# Controll_Board_SCH.net
KiCad netlist of a schematic drawn in Altium Designer
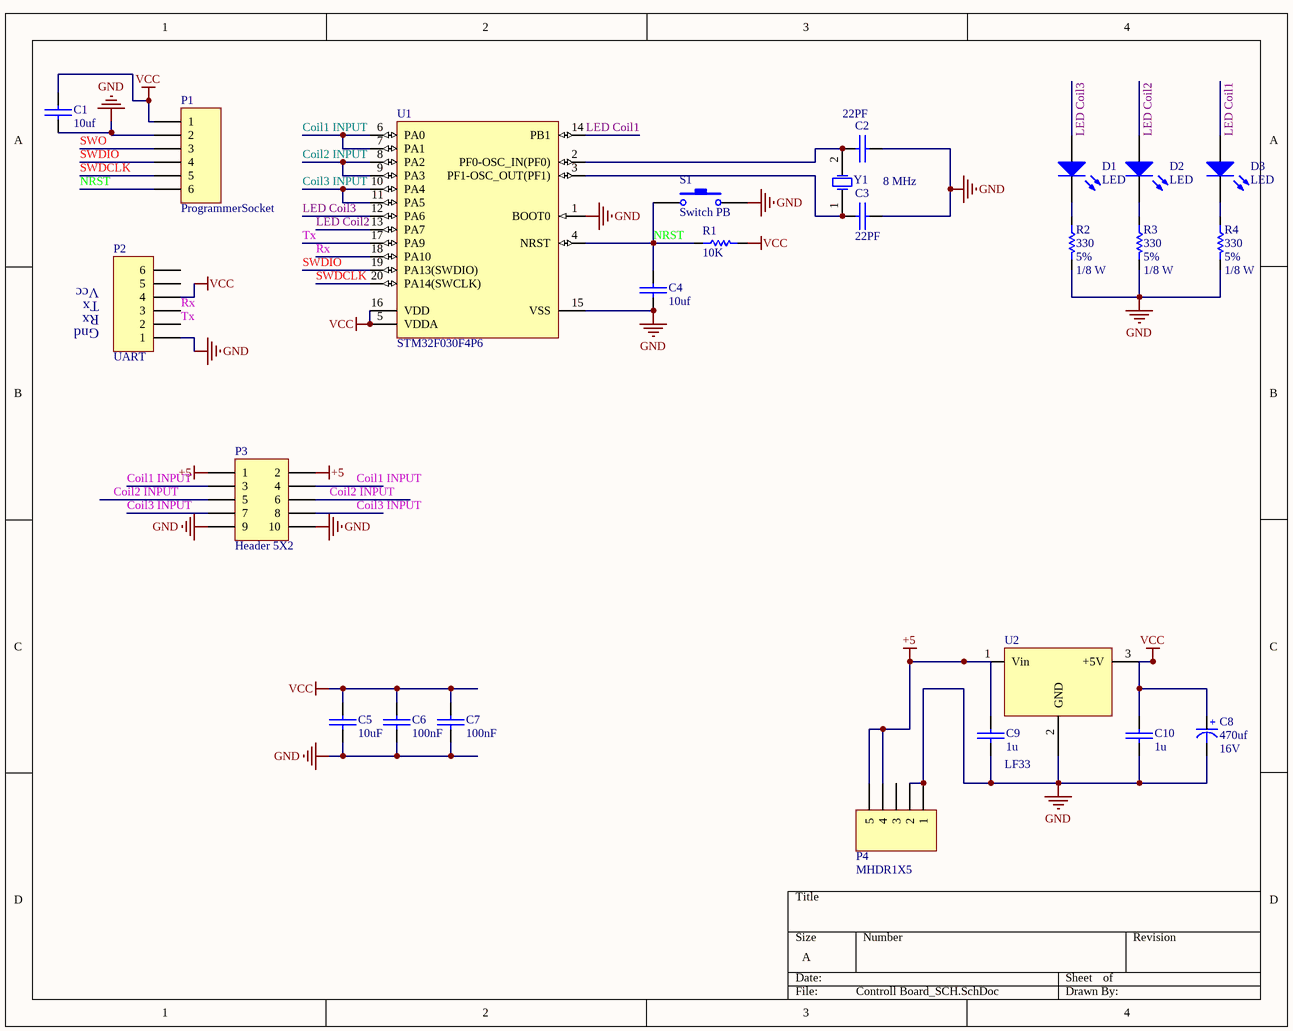
[diagram p0: Controll Board_SCH.SchDoc]

(export (version "E")
  (design (tool "Eeschema 10.0.6"))
  (components
    (comp (ref "C1")
      (value "10uf")
      (footprint "SMD_CAP_1206")
      (description "Bipolar Capacitor")
      (fields (field (name "VOLTAGE") "100V") (field (name "DESIGNER") "Saeid Jorablo"))
      (libsource (lib "My Library") (part "Cap-Bipolar"))
    )
    (comp (ref "C2")
      (value "22PF")
      (footprint "SMD_CAP_1206")
      (description "Bipolar Capacitor")
      (fields (field (name "VOLTAGE") "100V") (field (name "DESIGNER") "Saeid Jorablo"))
      (libsource (lib "My Library") (part "Cap-Bipolar"))
    )
    (comp (ref "C3")
      (value "22PF")
      (footprint "SMD_CAP_1206")
      (description "Bipolar Capacitor")
      (fields (field (name "VOLTAGE") "100V") (field (name "DESIGNER") "Saeid Jorablo"))
      (libsource (lib "My Library") (part "Cap-Bipolar"))
    )
    (comp (ref "C4")
      (value "10uf")
      (footprint "SMD_CAP_1206")
      (description "Bipolar Capacitor")
      (fields (field (name "VOLTAGE") "100V") (field (name "DESIGNER") "Saeid Jorablo"))
      (libsource (lib "My Library") (part "Cap-Bipolar"))
    )
    (comp (ref "C5")
      (value "10uF")
      (footprint "SMD_CAP_1206")
      (description "Bipolar Capacitor")
      (fields (field (name "VOLTAGE") "100V") (field (name "DESIGNER") "Saeid Jorablo"))
      (libsource (lib "My Library") (part "Cap-Bipolar"))
    )
    (comp (ref "C6")
      (value "100nF")
      (footprint "SMD_CAP_1206")
      (description "Bipolar Capacitor")
      (fields (field (name "VOLTAGE") "100V") (field (name "DESIGNER") "Saeid Jorablo"))
      (libsource (lib "My Library") (part "Cap-Bipolar"))
    )
    (comp (ref "C7")
      (value "100nF")
      (footprint "SMD_CAP_1206")
      (description "Bipolar Capacitor")
      (fields (field (name "VOLTAGE") "100V") (field (name "DESIGNER") "Saeid Jorablo"))
      (libsource (lib "My Library") (part "Cap-Bipolar"))
    )
    (comp (ref "C8")
      (value "470uf")
      (footprint "cap 01")
      (description "Polar Capacitor")
      (fields (field (name "VOLTAGE") "16V") (field (name "DESIGNER") "Saeid Jorablo"))
      (libsource (lib "My Library") (part "Cap-Polar"))
    )
    (comp (ref "C9")
      (value "1u")
      (footprint "SMD_CAP_1206")
      (description "Bipolar Capacitor")
      (fields (field (name "VOLTAGE") "100V") (field (name "DESIGNER") "Saeid Jorablo"))
      (libsource (lib "My Library") (part "Cap-Bipolar"))
    )
    (comp (ref "C10")
      (value "1u")
      (footprint "SMD_CAP_1206")
      (description "Bipolar Capacitor")
      (fields (field (name "VOLTAGE") "100V") (field (name "DESIGNER") "Saeid Jorablo"))
      (libsource (lib "My Library") (part "Cap-Bipolar"))
    )
    (comp (ref "D1")
      (value "LED")
      (footprint "My_LED3MM")
      (description "Typical INFRARED GaAs LED")
      (fields (field (name "PUBLISHER") "Altium Limited"))
      (libsource (lib "MyAltiumLib1") (part "LED"))
    )
    (comp (ref "D2")
      (value "LED")
      (footprint "My_LED3MM")
      (description "Typical INFRARED GaAs LED")
      (fields (field (name "PUBLISHER") "Altium Limited"))
      (libsource (lib "MyAltiumLib1") (part "LED"))
    )
    (comp (ref "D3")
      (value "LED")
      (footprint "My_LED3MM")
      (description "Typical INFRARED GaAs LED")
      (fields (field (name "PUBLISHER") "Altium Limited"))
      (libsource (lib "MyAltiumLib1") (part "LED"))
    )
    (comp (ref "P1")
      (value "ProgrammerSocket")
      (footprint "HDR1X6")
      (description "Header, 6-Pin")
      (fields (field (name "PUBLISHER") "Altium Limited"))
      (libsource (lib "") (part "Header 6_1"))
    )
    (comp (ref "P2")
      (value "UART")
      (footprint "HDR1X6")
      (description "Header, 6-Pin")
      (fields (field (name "PUBLISHER") "Altium Limited"))
      (libsource (lib "Miscellaneous Connectors") (part "Header 6"))
    )
    (comp (ref "P3")
      (value "Header 5X2")
      (footprint "HDR2X5")
      (description "Header, 5-Pin, Dual row")
      (fields (field (name "PUBLISHER") "Altium Limited"))
      (libsource (lib "Miscellaneous Connectors") (part "Header 5X2"))
    )
    (comp (ref "P4")
      (value "MHDR1X5")
      (footprint "MHDR1X5")
      (description "Header, 5-Pin")
      (fields (field (name "PUBLISHER") "Altium Limited"))
      (libsource (lib "Miscellaneous Connectors") (part "MHDR1X5"))
    )
    (comp (ref "R1")
      (value "10K")
      (footprint "RES 1206 (3216X08L)")
      (description "Resistor")
      (fields (field (name "TOLERANCE") "1%") (field (name "POWER") "1/8 W"))
      (libsource (lib "My Library") (part "Resistor"))
    )
    (comp (ref "R2")
      (value "330")
      (footprint "RES 1206 (3216X08L)")
      (description "Resistor")
      (fields (field (name "TOLERANCE") "5%") (field (name "POWER") "1/8 W"))
      (libsource (lib "My Library") (part "Resistor"))
    )
    (comp (ref "R3")
      (value "330")
      (footprint "RES 1206 (3216X08L)")
      (description "Resistor")
      (fields (field (name "TOLERANCE") "5%") (field (name "POWER") "1/8 W"))
      (libsource (lib "My Library") (part "Resistor"))
    )
    (comp (ref "R4")
      (value "330")
      (footprint "RES 1206 (3216X08L)")
      (description "Resistor")
      (fields (field (name "TOLERANCE") "5%") (field (name "POWER") "1/8 W"))
      (libsource (lib "My Library") (part "Resistor"))
    )
    (comp (ref "S1")
      (value "Switch PB")
      (footprint "Switch - Push to On")
      (description "Push Button Switch")
      (libsource (lib "My Library") (part "Switch PB"))
    )
    (comp (ref "U1")
      (value "STM32F030F4P6")
      (footprint "STM-TSSOP20_N")
      (libsource (lib "ST Microelectronics STM32 F0") (part "STM32F030F4P6"))
    )
    (comp (ref "U2")
      (value "LF33")
      (footprint "My_TO-220")
      (description "Regulator")
      (libsource (lib "Mylib") (part "7805"))
    )
    (comp (ref "Y1")
      (value "8 MHz")
      (footprint "XTAL Small")
      (description "XTAL Crystal")
      (libsource (lib "My Library") (part "XTAL"))
    )
  )
  (nets
    (net (code "1") (name "+5") (class "Default")
      (node (ref "C9") (pin "1") (pinfunction "+_1") (pintype "passive"))
      (node (ref "P3") (pin "1") (pinfunction "1_1") (pintype "passive"))
      (node (ref "P3") (pin "2") (pinfunction "2_2") (pintype "passive"))
      (node (ref "P4") (pin "4") (pinfunction "4_4") (pintype "passive"))
      (node (ref "P4") (pin "5") (pinfunction "5_5") (pintype "passive"))
      (node (ref "U2") (pin "1") (pinfunction "Vin_1") (pintype "power_in"))
    )
    (net (code "2") (name "/Coil1 INPUT") (class "Default")
      (node (ref "P3") (pin "3") (pinfunction "3_3") (pintype "passive"))
      (node (ref "P3") (pin "4") (pinfunction "4_4") (pintype "passive"))
      (node (ref "U1") (pin "6") (pinfunction "PA0_6") (pintype "bidirectional"))
      (node (ref "U1") (pin "7") (pinfunction "PA1_7") (pintype "bidirectional"))
    )
    (net (code "3") (name "/Coil2 INPUT") (class "Default")
      (node (ref "P3") (pin "5") (pinfunction "5_5") (pintype "passive"))
      (node (ref "P3") (pin "6") (pinfunction "6_6") (pintype "passive"))
      (node (ref "U1") (pin "8") (pinfunction "PA2_8") (pintype "bidirectional"))
      (node (ref "U1") (pin "9") (pinfunction "PA3_9") (pintype "bidirectional"))
    )
    (net (code "4") (name "/Coil3 INPUT") (class "Default")
      (node (ref "P3") (pin "7") (pinfunction "7_7") (pintype "passive"))
      (node (ref "P3") (pin "8") (pinfunction "8_8") (pintype "passive"))
      (node (ref "U1") (pin "10") (pinfunction "PA4_10") (pintype "bidirectional"))
      (node (ref "U1") (pin "11") (pinfunction "PA5_11") (pintype "bidirectional"))
    )
    (net (code "5") (name "/LED Coil1") (class "Default")
      (node (ref "D3") (pin "A") (pinfunction "A_A") (pintype "passive"))
      (node (ref "U1") (pin "14") (pinfunction "PB1_14") (pintype "bidirectional"))
    )
    (net (code "6") (name "/LED Coil2") (class "Default")
      (node (ref "D2") (pin "A") (pinfunction "A_A") (pintype "passive"))
      (node (ref "U1") (pin "13") (pinfunction "PA7_13") (pintype "bidirectional"))
    )
    (net (code "7") (name "/LED Coil3") (class "Default")
      (node (ref "D1") (pin "A") (pinfunction "A_A") (pintype "passive"))
      (node (ref "U1") (pin "12") (pinfunction "PA6_12") (pintype "bidirectional"))
    )
    (net (code "8") (name "/NRST") (class "Default")
      (node (ref "C4") (pin "2") (pinfunction "-_2") (pintype "passive"))
      (node (ref "P1") (pin "6") (pinfunction "6_6") (pintype "passive"))
      (node (ref "R1") (pin "1") (pinfunction "1_1") (pintype "passive"))
      (node (ref "S1") (pin "1") (pinfunction "1_1") (pintype "passive"))
      (node (ref "U1") (pin "4") (pinfunction "NRST_4") (pintype "bidirectional"))
    )
    (net (code "9") (name "/Rx") (class "Default")
      (node (ref "P2") (pin "3") (pinfunction "3_3") (pintype "passive"))
      (node (ref "U1") (pin "18") (pinfunction "PA10_18") (pintype "bidirectional"))
    )
    (net (code "10") (name "/SWDCLK") (class "Default")
      (node (ref "P1") (pin "5") (pinfunction "5_5") (pintype "passive"))
      (node (ref "U1") (pin "20") (pinfunction "PA14(SWCLK)_20") (pintype "bidirectional"))
    )
    (net (code "11") (name "/SWDIO") (class "Default")
      (node (ref "P1") (pin "4") (pinfunction "4_4") (pintype "passive"))
      (node (ref "U1") (pin "19") (pinfunction "PA13(SWDIO)_19") (pintype "bidirectional"))
    )
    (net (code "12") (name "/SWO") (class "Default")
      (node (ref "P1") (pin "3") (pinfunction "3_3") (pintype "passive"))
    )
    (net (code "13") (name "/Tx") (class "Default")
      (node (ref "P2") (pin "2") (pinfunction "2_2") (pintype "passive"))
      (node (ref "U1") (pin "17") (pinfunction "PA9_17") (pintype "bidirectional"))
    )
    (net (code "14") (name "GND") (class "Default")
      (node (ref "C1") (pin "1") (pinfunction "+_1") (pintype "passive"))
      (node (ref "C10") (pin "2") (pinfunction "-_2") (pintype "passive"))
      (node (ref "C2") (pin "2") (pinfunction "-_2") (pintype "passive"))
      (node (ref "C3") (pin "2") (pinfunction "-_2") (pintype "passive"))
      (node (ref "C4") (pin "1") (pinfunction "+_1") (pintype "passive"))
      (node (ref "C5") (pin "2") (pinfunction "-_2") (pintype "passive"))
      (node (ref "C6") (pin "2") (pinfunction "-_2") (pintype "passive"))
      (node (ref "C7") (pin "2") (pinfunction "-_2") (pintype "passive"))
      (node (ref "C8") (pin "2") (pinfunction "-_2") (pintype "passive"))
      (node (ref "C9") (pin "2") (pinfunction "-_2") (pintype "passive"))
      (node (ref "P1") (pin "2") (pinfunction "2_2") (pintype "passive"))
      (node (ref "P2") (pin "1") (pinfunction "1_1") (pintype "passive"))
      (node (ref "P3") (pin "10") (pinfunction "10_10") (pintype "passive"))
      (node (ref "P3") (pin "9") (pinfunction "9_9") (pintype "passive"))
      (node (ref "P4") (pin "1") (pinfunction "1_1") (pintype "passive"))
      (node (ref "P4") (pin "2") (pinfunction "2_2") (pintype "passive"))
      (node (ref "R2") (pin "2") (pinfunction "2_2") (pintype "passive"))
      (node (ref "R3") (pin "2") (pinfunction "2_2") (pintype "passive"))
      (node (ref "R4") (pin "2") (pinfunction "2_2") (pintype "passive"))
      (node (ref "S1") (pin "2") (pinfunction "2_2") (pintype "passive"))
      (node (ref "U1") (pin "1") (pinfunction "BOOT0_1") (pintype "input"))
      (node (ref "U1") (pin "15") (pinfunction "VSS_15") (pintype "power_in"))
      (node (ref "U2") (pin "2") (pinfunction "GND_2") (pintype "power_in"))
    )
    (net (code "15") (name "Net-(C2-+)") (class "Default")
      (node (ref "C2") (pin "1") (pinfunction "+_1") (pintype "passive"))
      (node (ref "U1") (pin "2") (pinfunction "PF0-OSC_IN(PF0)_2") (pintype "bidirectional"))
      (node (ref "Y1") (pin "2") (pinfunction "OSC2_2") (pintype "passive"))
    )
    (net (code "16") (name "Net-(C3-+)") (class "Default")
      (node (ref "C3") (pin "1") (pinfunction "+_1") (pintype "passive"))
      (node (ref "U1") (pin "3") (pinfunction "PF1-OSC_OUT(PF1)_3") (pintype "bidirectional"))
      (node (ref "Y1") (pin "1") (pinfunction "OSC1_1") (pintype "passive"))
    )
    (net (code "17") (name "Net-(D1-PadK)") (class "Default")
      (node (ref "D1") (pin "K") (pinfunction "K_K") (pintype "passive"))
      (node (ref "R2") (pin "1") (pinfunction "1_1") (pintype "passive"))
    )
    (net (code "18") (name "Net-(D2-PadK)") (class "Default")
      (node (ref "D2") (pin "K") (pinfunction "K_K") (pintype "passive"))
      (node (ref "R3") (pin "1") (pinfunction "1_1") (pintype "passive"))
    )
    (net (code "19") (name "Net-(D3-PadK)") (class "Default")
      (node (ref "D3") (pin "K") (pinfunction "K_K") (pintype "passive"))
      (node (ref "R4") (pin "1") (pinfunction "1_1") (pintype "passive"))
    )
    (net (code "20") (name "VCC") (class "Default")
      (node (ref "C1") (pin "2") (pinfunction "-_2") (pintype "passive"))
      (node (ref "C10") (pin "1") (pinfunction "+_1") (pintype "passive"))
      (node (ref "C5") (pin "1") (pinfunction "+_1") (pintype "passive"))
      (node (ref "C6") (pin "1") (pinfunction "+_1") (pintype "passive"))
      (node (ref "C7") (pin "1") (pinfunction "+_1") (pintype "passive"))
      (node (ref "C8") (pin "1") (pinfunction "+_1") (pintype "passive"))
      (node (ref "P1") (pin "1") (pinfunction "1_1") (pintype "passive"))
      (node (ref "P2") (pin "4") (pinfunction "4_4") (pintype "passive"))
      (node (ref "R1") (pin "2") (pinfunction "2_2") (pintype "passive"))
      (node (ref "U1") (pin "16") (pinfunction "VDD_16") (pintype "power_in"))
      (node (ref "U1") (pin "5") (pinfunction "VDDA_5") (pintype "power_in"))
      (node (ref "U2") (pin "3") (pinfunction "+5V_3") (pintype "power_in"))
    )
    (net (code "21") (name "unconnected-(P2-Pad5)") (class "Default")
      (node (ref "P2") (pin "5") (pinfunction "5_5") (pintype "passive"))
    )
    (net (code "22") (name "unconnected-(P2-Pad6)") (class "Default")
      (node (ref "P2") (pin "6") (pinfunction "6_6") (pintype "passive"))
    )
    (net (code "23") (name "unconnected-(P4-Pad3)") (class "Default")
      (node (ref "P4") (pin "3") (pinfunction "3_3") (pintype "passive"))
    )
  )
)
